# Schatten6.net
KiCad netlist of a schematic drawn in EAGLE
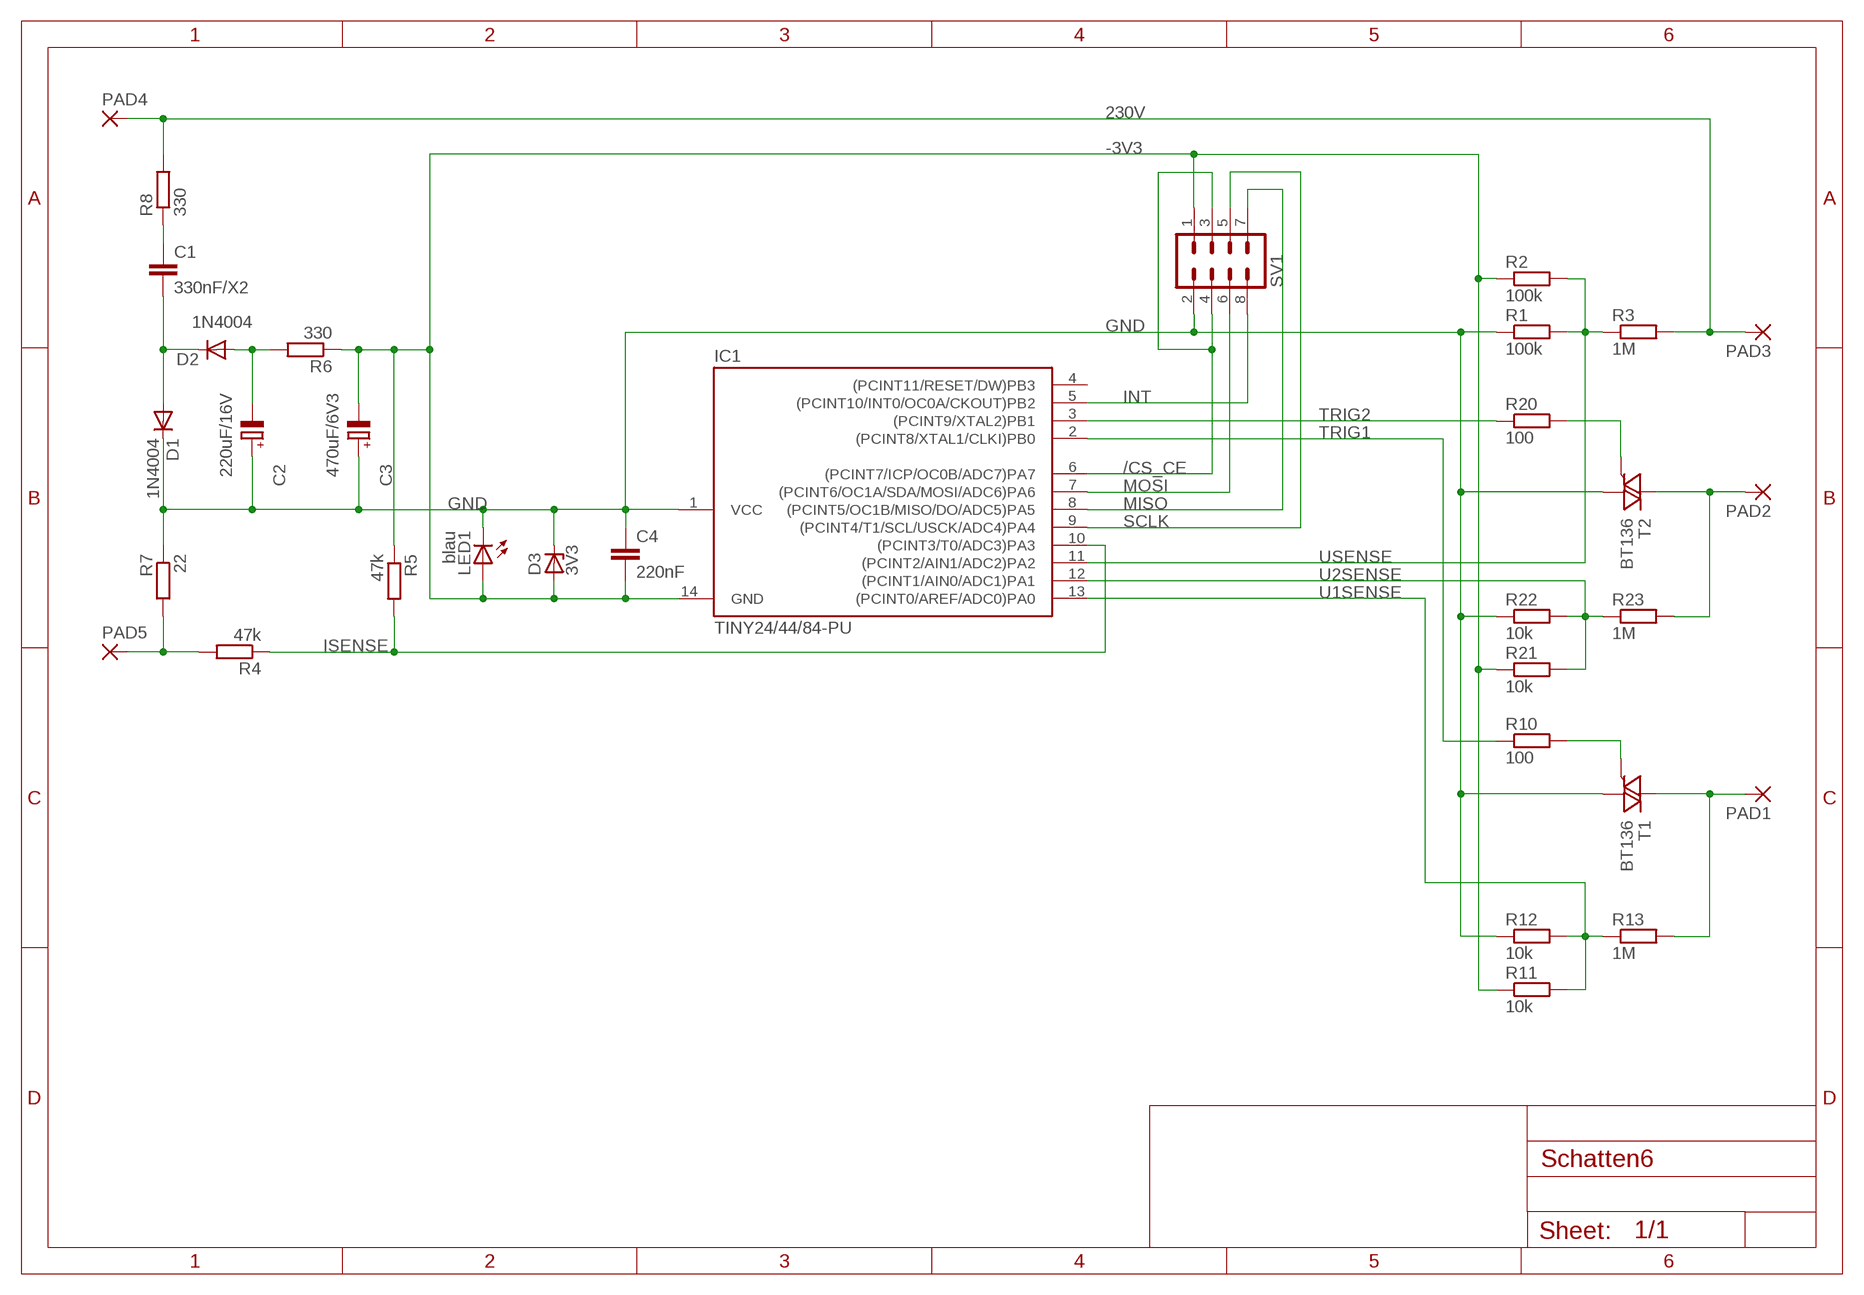
[diagram p0: schematic, sheet 1]

(export (version "E")
  (design (tool "Eeschema 10.0.6"))
  (components
    (comp (ref "C1")
      (value "330nF/X2")
      (footprint "eagle-import:C150-064X183")
      (libsource (lib "eagle-import") (part "C-EU150-064X183"))
    )
    (comp (ref "C2")
      (value "220uF/16V")
      (footprint "eagle-import:E5-8,5")
      (libsource (lib "eagle-import") (part "CPOL-EUE5-8.5"))
    )
    (comp (ref "C3")
      (value "470uF/6V3")
      (footprint "eagle-import:E5-8,5")
      (libsource (lib "eagle-import") (part "CPOL-EUE5-8.5"))
    )
    (comp (ref "C4")
      (value "220nF")
      (footprint "eagle-import:C3225")
      (libsource (lib "eagle-import") (part "C-EUC3225"))
    )
    (comp (ref "D1")
      (value "1N4004")
      (footprint "eagle-import:DO41-10")
      (libsource (lib "eagle-import") (part "1N4004"))
    )
    (comp (ref "D2")
      (value "1N4004")
      (footprint "eagle-import:DO41-10")
      (libsource (lib "eagle-import") (part "1N4004"))
    )
    (comp (ref "D3")
      (value "3V3")
      (footprint "eagle-import:ZDIO-7.5")
      (libsource (lib "eagle-import") (part "ZENER-DIODEZD-7.5"))
    )
    (comp (ref "IC1")
      (value "TINY24/44/84-PU")
      (footprint "eagle-import:DIL14")
      (libsource (lib "eagle-import") (part "TINY24/44/84-PU"))
    )
    (comp (ref "LED1")
      (value "blau")
      (footprint "eagle-import:LED3MM")
      (libsource (lib "eagle-import") (part "LED3MM"))
    )
    (comp (ref "PAD1")
      (value "1,6/0,9")
      (footprint "eagle-import:1,6_0,9")
      (libsource (lib "eagle-import") (part "1,6/0,9"))
    )
    (comp (ref "PAD2")
      (value "1,6/0,9")
      (footprint "eagle-import:1,6_0,9")
      (libsource (lib "eagle-import") (part "1,6/0,9"))
    )
    (comp (ref "PAD3")
      (value "1,6/0,9")
      (footprint "eagle-import:1,6_0,9")
      (libsource (lib "eagle-import") (part "1,6/0,9"))
    )
    (comp (ref "PAD4")
      (value "1,6/0,9")
      (footprint "eagle-import:1,6_0,9")
      (libsource (lib "eagle-import") (part "1,6/0,9"))
    )
    (comp (ref "PAD5")
      (value "1,6/0,9")
      (footprint "eagle-import:1,6_0,9")
      (libsource (lib "eagle-import") (part "1,6/0,9"))
    )
    (comp (ref "R1")
      (value "100k")
      (footprint "eagle-import:0207_10")
      (libsource (lib "eagle-import") (part "R-EU_0207/10"))
    )
    (comp (ref "R2")
      (value "100k")
      (footprint "eagle-import:0207_10")
      (libsource (lib "eagle-import") (part "R-EU_0207/10"))
    )
    (comp (ref "R3")
      (value "1M")
      (footprint "eagle-import:0207_10")
      (libsource (lib "eagle-import") (part "R-EU_0207/10"))
    )
    (comp (ref "R4")
      (value "47k")
      (footprint "eagle-import:0207_10")
      (libsource (lib "eagle-import") (part "R-EU_0207/10"))
    )
    (comp (ref "R5")
      (value "47k")
      (footprint "eagle-import:0204V")
      (libsource (lib "eagle-import") (part "R-EU_0204/2V"))
    )
    (comp (ref "R6")
      (value "330")
      (footprint "eagle-import:0207_10")
      (libsource (lib "eagle-import") (part "R-EU_0207/10"))
    )
    (comp (ref "R7")
      (value "22")
      (footprint "eagle-import:0207_10")
      (libsource (lib "eagle-import") (part "R-EU_0207/10"))
    )
    (comp (ref "R8")
      (value "330")
      (footprint "eagle-import:0207_10")
      (libsource (lib "eagle-import") (part "R-EU_0207/10"))
    )
    (comp (ref "R10")
      (value "100")
      (footprint "eagle-import:0207_10")
      (libsource (lib "eagle-import") (part "R-EU_0207/10"))
    )
    (comp (ref "R11")
      (value "10k")
      (footprint "eagle-import:0204_7")
      (libsource (lib "eagle-import") (part "R-EU_0204/7"))
    )
    (comp (ref "R12")
      (value "10k")
      (footprint "eagle-import:0207_10")
      (libsource (lib "eagle-import") (part "R-EU_0207/10"))
    )
    (comp (ref "R13")
      (value "1M")
      (footprint "eagle-import:0207_10")
      (libsource (lib "eagle-import") (part "R-EU_0207/10"))
    )
    (comp (ref "R20")
      (value "100")
      (footprint "eagle-import:0207_10")
      (libsource (lib "eagle-import") (part "R-EU_0207/10"))
    )
    (comp (ref "R21")
      (value "10k")
      (footprint "eagle-import:0207_10")
      (libsource (lib "eagle-import") (part "R-EU_0207/10"))
    )
    (comp (ref "R22")
      (value "10k")
      (footprint "eagle-import:0207_10")
      (libsource (lib "eagle-import") (part "R-EU_0207/10"))
    )
    (comp (ref "R23")
      (value "1M")
      (footprint "eagle-import:0207_10")
      (libsource (lib "eagle-import") (part "R-EU_0207/10"))
    )
    (comp (ref "SV1")
      (value "MA04-2")
      (footprint "eagle-import:MA04-2")
      (libsource (lib "eagle-import") (part "MA04-2"))
    )
    (comp (ref "T1")
      (value "BT136")
      (footprint "eagle-import:TO220AB")
      (libsource (lib "eagle-import") (part "BT136"))
    )
    (comp (ref "T2")
      (value "BT136")
      (footprint "eagle-import:TO220AB")
      (libsource (lib "eagle-import") (part "BT136"))
    )
  )
  (nets
    (net (code "1") (name "/-3V3") (class "Default")
      (node (ref "C3") (pin "-") (pinfunction "-_-") (pintype "passive"))
      (node (ref "C4") (pin "2") (pinfunction "2_2") (pintype "passive"))
      (node (ref "D3") (pin "A") (pinfunction "A_A") (pintype "passive"))
      (node (ref "IC1") (pin "14") (pinfunction "GND_14") (pintype "power_in"))
      (node (ref "LED1") (pin "A") (pinfunction "A_A") (pintype "passive"))
      (node (ref "R11") (pin "1") (pinfunction "1_1") (pintype "passive"))
      (node (ref "R2") (pin "1") (pinfunction "1_1") (pintype "passive"))
      (node (ref "R21") (pin "1") (pinfunction "1_1") (pintype "passive"))
      (node (ref "R5") (pin "1") (pinfunction "1_1") (pintype "passive"))
      (node (ref "R6") (pin "1") (pinfunction "1_1") (pintype "passive"))
      (node (ref "SV1") (pin "1") (pinfunction "1_1") (pintype "passive"))
    )
    (net (code "2") (name "/230V") (class "Default")
      (node (ref "PAD3") (pin "1") (pinfunction "P_1") (pintype "passive"))
      (node (ref "PAD4") (pin "1") (pinfunction "P_1") (pintype "passive"))
      (node (ref "R3") (pin "2") (pinfunction "2_2") (pintype "passive"))
      (node (ref "R8") (pin "2") (pinfunction "2_2") (pintype "passive"))
    )
    (net (code "3") (name "/GND") (class "Default")
      (node (ref "C2") (pin "+") (pinfunction "+_+") (pintype "passive"))
      (node (ref "C3") (pin "+") (pinfunction "+_+") (pintype "passive"))
      (node (ref "C4") (pin "1") (pinfunction "1_1") (pintype "passive"))
      (node (ref "D1") (pin "C") (pinfunction "C_C") (pintype "passive"))
      (node (ref "D3") (pin "C") (pinfunction "C_C") (pintype "passive"))
      (node (ref "IC1") (pin "1") (pinfunction "VCC_1") (pintype "power_in"))
      (node (ref "LED1") (pin "K") (pinfunction "C_K") (pintype "passive"))
      (node (ref "R1") (pin "1") (pinfunction "1_1") (pintype "passive"))
      (node (ref "R12") (pin "1") (pinfunction "1_1") (pintype "passive"))
      (node (ref "R22") (pin "1") (pinfunction "1_1") (pintype "passive"))
      (node (ref "R7") (pin "1") (pinfunction "1_1") (pintype "passive"))
      (node (ref "SV1") (pin "2") (pinfunction "2_2") (pintype "passive"))
      (node (ref "T1") (pin "1") (pinfunction "A1_1") (pintype "passive"))
      (node (ref "T2") (pin "1") (pinfunction "A1_1") (pintype "passive"))
    )
    (net (code "4") (name "/INT") (class "Default")
      (node (ref "IC1") (pin "5") (pinfunction "(PCINT10/INT0/OC0A/CKOUT)PB2_5") (pintype "bidirectional"))
      (node (ref "SV1") (pin "8") (pinfunction "8_8") (pintype "passive"))
    )
    (net (code "5") (name "/ISENSE") (class "Default")
      (node (ref "IC1") (pin "10") (pinfunction "(PCINT3/T0/ADC3)PA3_10") (pintype "bidirectional"))
      (node (ref "R4") (pin "1") (pinfunction "1_1") (pintype "passive"))
      (node (ref "R5") (pin "2") (pinfunction "2_2") (pintype "passive"))
    )
    (net (code "6") (name "/MISO") (class "Default")
      (node (ref "IC1") (pin "8") (pinfunction "(PCINT5/OC1B/MISO/DO/ADC5)PA5_8") (pintype "bidirectional"))
      (node (ref "SV1") (pin "7") (pinfunction "7_7") (pintype "passive"))
    )
    (net (code "7") (name "/MOSI") (class "Default")
      (node (ref "IC1") (pin "7") (pinfunction "(PCINT6/OC1A/SDA/MOSI/ADC6)PA6_7") (pintype "bidirectional"))
      (node (ref "SV1") (pin "6") (pinfunction "6_6") (pintype "passive"))
    )
    (net (code "8") (name "/SCLK") (class "Default")
      (node (ref "IC1") (pin "9") (pinfunction "(PCINT4/T1/SCL/USCK/ADC4)PA4_9") (pintype "bidirectional"))
      (node (ref "SV1") (pin "5") (pinfunction "5_5") (pintype "passive"))
    )
    (net (code "9") (name "/TRIG1") (class "Default")
      (node (ref "IC1") (pin "2") (pinfunction "(PCINT8/XTAL1/CLKI)PB0_2") (pintype "bidirectional"))
      (node (ref "R10") (pin "1") (pinfunction "1_1") (pintype "passive"))
    )
    (net (code "10") (name "/TRIG2") (class "Default")
      (node (ref "IC1") (pin "3") (pinfunction "(PCINT9/XTAL2)PB1_3") (pintype "bidirectional"))
      (node (ref "R20") (pin "1") (pinfunction "1_1") (pintype "passive"))
    )
    (net (code "11") (name "/U1SENSE") (class "Default")
      (node (ref "IC1") (pin "13") (pinfunction "(PCINT0/AREF/ADC0)PA0_13") (pintype "bidirectional"))
      (node (ref "R11") (pin "2") (pinfunction "2_2") (pintype "passive"))
      (node (ref "R12") (pin "2") (pinfunction "2_2") (pintype "passive"))
      (node (ref "R13") (pin "1") (pinfunction "1_1") (pintype "passive"))
    )
    (net (code "12") (name "/U2SENSE") (class "Default")
      (node (ref "IC1") (pin "12") (pinfunction "(PCINT1/AIN0/ADC1)PA1_12") (pintype "bidirectional"))
      (node (ref "R21") (pin "2") (pinfunction "2_2") (pintype "passive"))
      (node (ref "R22") (pin "2") (pinfunction "2_2") (pintype "passive"))
      (node (ref "R23") (pin "1") (pinfunction "1_1") (pintype "passive"))
    )
    (net (code "13") (name "/USENSE") (class "Default")
      (node (ref "IC1") (pin "11") (pinfunction "(PCINT2/AIN1/ADC2)PA2_11") (pintype "bidirectional"))
      (node (ref "R1") (pin "2") (pinfunction "2_2") (pintype "passive"))
      (node (ref "R2") (pin "2") (pinfunction "2_2") (pintype "passive"))
      (node (ref "R3") (pin "1") (pinfunction "1_1") (pintype "passive"))
    )
    (net (code "14") (name "/{slash}CS_CE") (class "Default")
      (node (ref "IC1") (pin "6") (pinfunction "(PCINT7/ICP/OC0B/ADC7)PA7_6") (pintype "bidirectional"))
      (node (ref "SV1") (pin "3") (pinfunction "3_3") (pintype "passive"))
      (node (ref "SV1") (pin "4") (pinfunction "4_4") (pintype "passive"))
    )
    (net (code "15") (name "Net-(C1-Pad1)") (class "Default")
      (node (ref "C1") (pin "1") (pinfunction "1_1") (pintype "passive"))
      (node (ref "R8") (pin "1") (pinfunction "1_1") (pintype "passive"))
    )
    (net (code "16") (name "Net-(C1-Pad2)") (class "Default")
      (node (ref "C1") (pin "2") (pinfunction "2_2") (pintype "passive"))
      (node (ref "D1") (pin "A") (pinfunction "A_A") (pintype "passive"))
      (node (ref "D2") (pin "C") (pinfunction "C_C") (pintype "passive"))
    )
    (net (code "17") (name "Net-(C2-Pad-)") (class "Default")
      (node (ref "C2") (pin "-") (pinfunction "-_-") (pintype "passive"))
      (node (ref "D2") (pin "A") (pinfunction "A_A") (pintype "passive"))
      (node (ref "R6") (pin "2") (pinfunction "2_2") (pintype "passive"))
    )
    (net (code "18") (name "Net-(PAD1-P)") (class "Default")
      (node (ref "PAD1") (pin "1") (pinfunction "P_1") (pintype "passive"))
      (node (ref "R13") (pin "2") (pinfunction "2_2") (pintype "passive"))
      (node (ref "T1") (pin "2") (pinfunction "A2_2") (pintype "passive"))
    )
    (net (code "19") (name "Net-(PAD2-P)") (class "Default")
      (node (ref "PAD2") (pin "1") (pinfunction "P_1") (pintype "passive"))
      (node (ref "R23") (pin "2") (pinfunction "2_2") (pintype "passive"))
      (node (ref "T2") (pin "2") (pinfunction "A2_2") (pintype "passive"))
    )
    (net (code "20") (name "Net-(PAD5-P)") (class "Default")
      (node (ref "PAD5") (pin "1") (pinfunction "P_1") (pintype "passive"))
      (node (ref "R4") (pin "2") (pinfunction "2_2") (pintype "passive"))
      (node (ref "R7") (pin "2") (pinfunction "2_2") (pintype "passive"))
    )
    (net (code "21") (name "Net-(T1-G)") (class "Default")
      (node (ref "R10") (pin "2") (pinfunction "2_2") (pintype "passive"))
      (node (ref "T1") (pin "3") (pinfunction "G_3") (pintype "passive"))
    )
    (net (code "22") (name "Net-(T2-G)") (class "Default")
      (node (ref "R20") (pin "2") (pinfunction "2_2") (pintype "passive"))
      (node (ref "T2") (pin "3") (pinfunction "G_3") (pintype "passive"))
    )
    (net (code "23") (name "unconnected-(IC1-(PCINT11{slash}RESET{slash}DW)PB3-Pad4)") (class "Default")
      (node (ref "IC1") (pin "4") (pinfunction "(PCINT11/RESET/DW)PB3_4") (pintype "bidirectional"))
    )
  )
)
